# Front_panel.net
KiCad netlist of a schematic drawn in Altium Designer
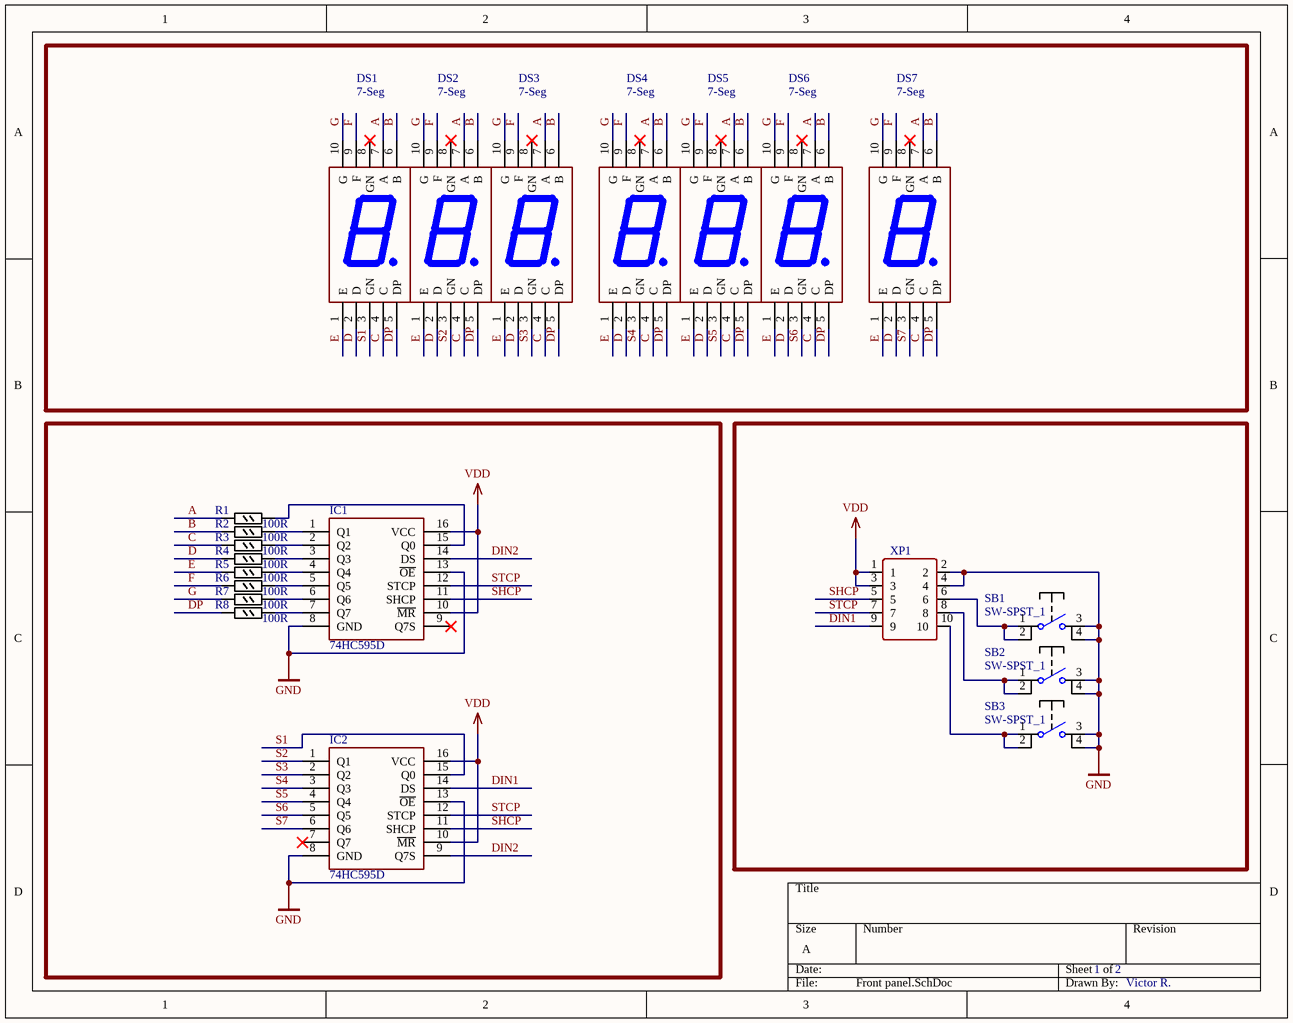
[diagram p0: Front panel.SchDoc]

(export (version "E")
  (design (tool "Eeschema 10.0.6"))
  (components
    (comp (ref "DS1")
      (value "7-Seg")
      (footprint "SamacSys:DIPS1524W51P254L1260H800Q10N")
      (description "Display")
      (fields (field (name "MANUFACTURER_PART_NUMBER") "4258"))
      (libsource (lib "SamacSys") (part "7-Seg"))
    )
    (comp (ref "DS2")
      (value "7-Seg")
      (footprint "SamacSys:DIPS1524W51P254L1260H800Q10N")
      (description "Display")
      (fields (field (name "MANUFACTURER_PART_NUMBER") "4258"))
      (libsource (lib "SamacSys") (part "7-Seg"))
    )
    (comp (ref "DS3")
      (value "7-Seg")
      (footprint "SamacSys:DIPS1524W51P254L1260H800Q10N")
      (description "Display")
      (fields (field (name "MANUFACTURER_PART_NUMBER") "4258"))
      (libsource (lib "SamacSys") (part "7-Seg"))
    )
    (comp (ref "DS4")
      (value "7-Seg")
      (footprint "SamacSys:DIPS1524W51P254L1260H800Q10N")
      (description "Display")
      (fields (field (name "MANUFACTURER_PART_NUMBER") "4258"))
      (libsource (lib "SamacSys") (part "7-Seg"))
    )
    (comp (ref "DS5")
      (value "7-Seg")
      (footprint "SamacSys:DIPS1524W51P254L1260H800Q10N")
      (description "Display")
      (fields (field (name "MANUFACTURER_PART_NUMBER") "4258"))
      (libsource (lib "SamacSys") (part "7-Seg"))
    )
    (comp (ref "DS6")
      (value "7-Seg")
      (footprint "SamacSys:DIPS1524W51P254L1260H800Q10N")
      (description "Display")
      (fields (field (name "MANUFACTURER_PART_NUMBER") "4258"))
      (libsource (lib "SamacSys") (part "7-Seg"))
    )
    (comp (ref "DS7")
      (value "7-Seg")
      (footprint "SamacSys:DIPS1524W51P254L1260H800Q10N")
      (description "Display")
      (fields (field (name "MANUFACTURER_PART_NUMBER") "4258"))
      (libsource (lib "SamacSys") (part "7-Seg"))
    )
    (comp (ref "IC1")
      (value "74HC595D")
      (footprint "SamacSys:SOIC127P600X175-16N")
      (description "Integrated Circuit")
      (libsource (lib "SamacSys") (part "74HC595D"))
    )
    (comp (ref "IC2")
      (value "74HC595D")
      (footprint "SamacSys:SOIC127P600X175-16N")
      (description "Integrated Circuit")
      (libsource (lib "SamacSys") (part "74HC595D"))
    )
    (comp (ref "R1")
      (value "100R")
      (footprint "RESC2012(0805)N")
      (fields (field (name "PART NUMBER") "RESC2012(0805)"))
      (libsource (lib "SssAccesDatbase") (part "Resistor 0,125W"))
    )
    (comp (ref "R2")
      (value "100R")
      (footprint "RESC2012(0805)N")
      (fields (field (name "PART NUMBER") "RESC2012(0805)"))
      (libsource (lib "SssAccesDatbase") (part "Resistor 0,125W"))
    )
    (comp (ref "R3")
      (value "100R")
      (footprint "RESC2012(0805)N")
      (fields (field (name "PART NUMBER") "RESC2012(0805)"))
      (libsource (lib "SssAccesDatbase") (part "Resistor 0,125W"))
    )
    (comp (ref "R4")
      (value "100R")
      (footprint "RESC2012(0805)N")
      (fields (field (name "PART NUMBER") "RESC2012(0805)"))
      (libsource (lib "SssAccesDatbase") (part "Resistor 0,125W"))
    )
    (comp (ref "R5")
      (value "100R")
      (footprint "RESC2012(0805)N")
      (fields (field (name "PART NUMBER") "RESC2012(0805)"))
      (libsource (lib "SssAccesDatbase") (part "Resistor 0,125W"))
    )
    (comp (ref "R6")
      (value "100R")
      (footprint "RESC2012(0805)N")
      (fields (field (name "PART NUMBER") "RESC2012(0805)"))
      (libsource (lib "SssAccesDatbase") (part "Resistor 0,125W"))
    )
    (comp (ref "R7")
      (value "100R")
      (footprint "RESC2012(0805)N")
      (fields (field (name "PART NUMBER") "RESC2012(0805)"))
      (libsource (lib "SssAccesDatbase") (part "Resistor 0,125W"))
    )
    (comp (ref "R8")
      (value "100R")
      (footprint "RESC2012(0805)N")
      (fields (field (name "PART NUMBER") "RESC2012(0805)"))
      (libsource (lib "SssAccesDatbase") (part "Resistor 0,125W"))
    )
    (comp (ref "SB1")
      (value "SW-SPST_1")
      (footprint "B3FS_SWITCH")
      (libsource (lib "SssAccesDatbase") (part "SW-SPST_1"))
    )
    (comp (ref "SB2")
      (value "SW-SPST_1")
      (footprint "B3FS_SWITCH")
      (libsource (lib "SssAccesDatbase") (part "SW-SPST_1"))
    )
    (comp (ref "SB3")
      (value "SW-SPST_1")
      (footprint "B3FS_SWITCH")
      (libsource (lib "SssAccesDatbase") (part "SW-SPST_1"))
    )
    (comp (ref "XP1")
      (value "BH-10")
      (footprint "BH-10")
      (description "Connector Header Through Hole 10 position 0.100\" (2.54mm)")
      (fields (field (name "PART NUMBER") "302-S101") (field (name "DIGI-KEY PART NUMBER") "ED1543-ND"))
      (libsource (lib "SssAccesDatbase") (part "XP-10"))
    )
  )
  (nets
    (net (code "1") (name "/A") (class "Default")
      (node (ref "DS1") (pin "7") (pinfunction "A_7") (pintype "passive"))
      (node (ref "DS2") (pin "7") (pinfunction "A_7") (pintype "passive"))
      (node (ref "DS3") (pin "7") (pinfunction "A_7") (pintype "passive"))
      (node (ref "DS4") (pin "7") (pinfunction "A_7") (pintype "passive"))
      (node (ref "DS5") (pin "7") (pinfunction "A_7") (pintype "passive"))
      (node (ref "DS6") (pin "7") (pinfunction "A_7") (pintype "passive"))
      (node (ref "DS7") (pin "7") (pinfunction "A_7") (pintype "passive"))
      (node (ref "R1") (pin "1") (pinfunction "1_1") (pintype "passive"))
    )
    (net (code "2") (name "/B") (class "Default")
      (node (ref "DS1") (pin "6") (pinfunction "B_6") (pintype "passive"))
      (node (ref "DS2") (pin "6") (pinfunction "B_6") (pintype "passive"))
      (node (ref "DS3") (pin "6") (pinfunction "B_6") (pintype "passive"))
      (node (ref "DS4") (pin "6") (pinfunction "B_6") (pintype "passive"))
      (node (ref "DS5") (pin "6") (pinfunction "B_6") (pintype "passive"))
      (node (ref "DS6") (pin "6") (pinfunction "B_6") (pintype "passive"))
      (node (ref "DS7") (pin "6") (pinfunction "B_6") (pintype "passive"))
      (node (ref "R2") (pin "1") (pinfunction "1_1") (pintype "passive"))
    )
    (net (code "3") (name "/C") (class "Default")
      (node (ref "DS1") (pin "4") (pinfunction "C_4") (pintype "passive"))
      (node (ref "DS2") (pin "4") (pinfunction "C_4") (pintype "passive"))
      (node (ref "DS3") (pin "4") (pinfunction "C_4") (pintype "passive"))
      (node (ref "DS4") (pin "4") (pinfunction "C_4") (pintype "passive"))
      (node (ref "DS5") (pin "4") (pinfunction "C_4") (pintype "passive"))
      (node (ref "DS6") (pin "4") (pinfunction "C_4") (pintype "passive"))
      (node (ref "DS7") (pin "4") (pinfunction "C_4") (pintype "passive"))
      (node (ref "R3") (pin "1") (pinfunction "1_1") (pintype "passive"))
    )
    (net (code "4") (name "/D") (class "Default")
      (node (ref "DS1") (pin "2") (pinfunction "D_2") (pintype "passive"))
      (node (ref "DS2") (pin "2") (pinfunction "D_2") (pintype "passive"))
      (node (ref "DS3") (pin "2") (pinfunction "D_2") (pintype "passive"))
      (node (ref "DS4") (pin "2") (pinfunction "D_2") (pintype "passive"))
      (node (ref "DS5") (pin "2") (pinfunction "D_2") (pintype "passive"))
      (node (ref "DS6") (pin "2") (pinfunction "D_2") (pintype "passive"))
      (node (ref "DS7") (pin "2") (pinfunction "D_2") (pintype "passive"))
      (node (ref "R4") (pin "1") (pinfunction "1_1") (pintype "passive"))
    )
    (net (code "5") (name "/DIN1") (class "Default")
      (node (ref "IC2") (pin "14") (pinfunction "DS_14") (pintype "passive"))
      (node (ref "XP1") (pin "9") (pinfunction "9_9") (pintype "passive"))
    )
    (net (code "6") (name "/DIN2") (class "Default")
      (node (ref "IC1") (pin "14") (pinfunction "DS_14") (pintype "passive"))
      (node (ref "IC2") (pin "9") (pinfunction "Q7S_9") (pintype "passive"))
    )
    (net (code "7") (name "/DP") (class "Default")
      (node (ref "DS1") (pin "5") (pinfunction "DP_5") (pintype "passive"))
      (node (ref "DS2") (pin "5") (pinfunction "DP_5") (pintype "passive"))
      (node (ref "DS3") (pin "5") (pinfunction "DP_5") (pintype "passive"))
      (node (ref "DS4") (pin "5") (pinfunction "DP_5") (pintype "passive"))
      (node (ref "DS5") (pin "5") (pinfunction "DP_5") (pintype "passive"))
      (node (ref "DS6") (pin "5") (pinfunction "DP_5") (pintype "passive"))
      (node (ref "DS7") (pin "5") (pinfunction "DP_5") (pintype "passive"))
      (node (ref "R8") (pin "1") (pinfunction "1_1") (pintype "passive"))
    )
    (net (code "8") (name "/E") (class "Default")
      (node (ref "DS1") (pin "1") (pinfunction "E_1") (pintype "passive"))
      (node (ref "DS2") (pin "1") (pinfunction "E_1") (pintype "passive"))
      (node (ref "DS3") (pin "1") (pinfunction "E_1") (pintype "passive"))
      (node (ref "DS4") (pin "1") (pinfunction "E_1") (pintype "passive"))
      (node (ref "DS5") (pin "1") (pinfunction "E_1") (pintype "passive"))
      (node (ref "DS6") (pin "1") (pinfunction "E_1") (pintype "passive"))
      (node (ref "DS7") (pin "1") (pinfunction "E_1") (pintype "passive"))
      (node (ref "R5") (pin "1") (pinfunction "1_1") (pintype "passive"))
    )
    (net (code "9") (name "/F") (class "Default")
      (node (ref "DS1") (pin "9") (pinfunction "F_9") (pintype "passive"))
      (node (ref "DS2") (pin "9") (pinfunction "F_9") (pintype "passive"))
      (node (ref "DS3") (pin "9") (pinfunction "F_9") (pintype "passive"))
      (node (ref "DS4") (pin "9") (pinfunction "F_9") (pintype "passive"))
      (node (ref "DS5") (pin "9") (pinfunction "F_9") (pintype "passive"))
      (node (ref "DS6") (pin "9") (pinfunction "F_9") (pintype "passive"))
      (node (ref "DS7") (pin "9") (pinfunction "F_9") (pintype "passive"))
      (node (ref "R6") (pin "1") (pinfunction "1_1") (pintype "passive"))
    )
    (net (code "10") (name "/G") (class "Default")
      (node (ref "DS1") (pin "10") (pinfunction "G_10") (pintype "passive"))
      (node (ref "DS2") (pin "10") (pinfunction "G_10") (pintype "passive"))
      (node (ref "DS3") (pin "10") (pinfunction "G_10") (pintype "passive"))
      (node (ref "DS4") (pin "10") (pinfunction "G_10") (pintype "passive"))
      (node (ref "DS5") (pin "10") (pinfunction "G_10") (pintype "passive"))
      (node (ref "DS6") (pin "10") (pinfunction "G_10") (pintype "passive"))
      (node (ref "DS7") (pin "10") (pinfunction "G_10") (pintype "passive"))
      (node (ref "R7") (pin "1") (pinfunction "1_1") (pintype "passive"))
    )
    (net (code "11") (name "/S1") (class "Default")
      (node (ref "DS1") (pin "3") (pinfunction "GN_3") (pintype "passive"))
      (node (ref "IC2") (pin "15") (pinfunction "Q0_15") (pintype "passive"))
    )
    (net (code "12") (name "/S2") (class "Default")
      (node (ref "DS2") (pin "3") (pinfunction "GN_3") (pintype "passive"))
      (node (ref "IC2") (pin "1") (pinfunction "Q1_1") (pintype "passive"))
    )
    (net (code "13") (name "/S3") (class "Default")
      (node (ref "DS3") (pin "3") (pinfunction "GN_3") (pintype "passive"))
      (node (ref "IC2") (pin "2") (pinfunction "Q2_2") (pintype "passive"))
    )
    (net (code "14") (name "/S4") (class "Default")
      (node (ref "DS4") (pin "3") (pinfunction "GN_3") (pintype "passive"))
      (node (ref "IC2") (pin "3") (pinfunction "Q3_3") (pintype "passive"))
    )
    (net (code "15") (name "/S5") (class "Default")
      (node (ref "DS5") (pin "3") (pinfunction "GN_3") (pintype "passive"))
      (node (ref "IC2") (pin "4") (pinfunction "Q4_4") (pintype "passive"))
    )
    (net (code "16") (name "/S6") (class "Default")
      (node (ref "DS6") (pin "3") (pinfunction "GN_3") (pintype "passive"))
      (node (ref "IC2") (pin "5") (pinfunction "Q5_5") (pintype "passive"))
    )
    (net (code "17") (name "/S7") (class "Default")
      (node (ref "DS7") (pin "3") (pinfunction "GN_3") (pintype "passive"))
      (node (ref "IC2") (pin "6") (pinfunction "Q6_6") (pintype "passive"))
    )
    (net (code "18") (name "/SHCP") (class "Default")
      (node (ref "IC1") (pin "11") (pinfunction "SHCP_11") (pintype "passive"))
      (node (ref "IC2") (pin "11") (pinfunction "SHCP_11") (pintype "passive"))
      (node (ref "XP1") (pin "5") (pinfunction "5_5") (pintype "passive"))
    )
    (net (code "19") (name "/STCP") (class "Default")
      (node (ref "IC1") (pin "12") (pinfunction "STCP_12") (pintype "passive"))
      (node (ref "IC2") (pin "12") (pinfunction "STCP_12") (pintype "passive"))
      (node (ref "XP1") (pin "7") (pinfunction "7_7") (pintype "passive"))
    )
    (net (code "20") (name "GND") (class "Default")
      (node (ref "IC1") (pin "13") (pinfunction "~{OE}_13") (pintype "passive"))
      (node (ref "IC1") (pin "8") (pinfunction "GND_8") (pintype "passive"))
      (node (ref "IC2") (pin "13") (pinfunction "~{OE}_13") (pintype "passive"))
      (node (ref "IC2") (pin "8") (pinfunction "GND_8") (pintype "passive"))
      (node (ref "SB1") (pin "3") (pinfunction "COMMON_3") (pintype "passive"))
      (node (ref "SB1") (pin "4") (pinfunction "COMMON_4") (pintype "passive"))
      (node (ref "SB2") (pin "3") (pinfunction "COMMON_3") (pintype "passive"))
      (node (ref "SB2") (pin "4") (pinfunction "COMMON_4") (pintype "passive"))
      (node (ref "SB3") (pin "3") (pinfunction "COMMON_3") (pintype "passive"))
      (node (ref "SB3") (pin "4") (pinfunction "COMMON_4") (pintype "passive"))
      (node (ref "XP1") (pin "2") (pinfunction "2_2") (pintype "passive"))
      (node (ref "XP1") (pin "4") (pinfunction "4_4") (pintype "passive"))
    )
    (net (code "21") (name "Net-(IC1-Q0)") (class "Default")
      (node (ref "IC1") (pin "15") (pinfunction "Q0_15") (pintype "passive"))
      (node (ref "R1") (pin "2") (pinfunction "2_2") (pintype "passive"))
    )
    (net (code "22") (name "Net-(IC1-Q1)") (class "Default")
      (node (ref "IC1") (pin "1") (pinfunction "Q1_1") (pintype "passive"))
      (node (ref "R2") (pin "2") (pinfunction "2_2") (pintype "passive"))
    )
    (net (code "23") (name "Net-(IC1-Q2)") (class "Default")
      (node (ref "IC1") (pin "2") (pinfunction "Q2_2") (pintype "passive"))
      (node (ref "R3") (pin "2") (pinfunction "2_2") (pintype "passive"))
    )
    (net (code "24") (name "Net-(IC1-Q3)") (class "Default")
      (node (ref "IC1") (pin "3") (pinfunction "Q3_3") (pintype "passive"))
      (node (ref "R4") (pin "2") (pinfunction "2_2") (pintype "passive"))
    )
    (net (code "25") (name "Net-(IC1-Q4)") (class "Default")
      (node (ref "IC1") (pin "4") (pinfunction "Q4_4") (pintype "passive"))
      (node (ref "R5") (pin "2") (pinfunction "2_2") (pintype "passive"))
    )
    (net (code "26") (name "Net-(IC1-Q5)") (class "Default")
      (node (ref "IC1") (pin "5") (pinfunction "Q5_5") (pintype "passive"))
      (node (ref "R6") (pin "2") (pinfunction "2_2") (pintype "passive"))
    )
    (net (code "27") (name "Net-(IC1-Q6)") (class "Default")
      (node (ref "IC1") (pin "6") (pinfunction "Q6_6") (pintype "passive"))
      (node (ref "R7") (pin "2") (pinfunction "2_2") (pintype "passive"))
    )
    (net (code "28") (name "Net-(IC1-Q7)") (class "Default")
      (node (ref "IC1") (pin "7") (pinfunction "Q7_7") (pintype "passive"))
      (node (ref "R8") (pin "2") (pinfunction "2_2") (pintype "passive"))
    )
    (net (code "29") (name "Net-(SB1-NO)") (class "Default")
      (node (ref "SB1") (pin "1") (pinfunction "COMMON_1") (pintype "passive"))
      (node (ref "SB1") (pin "2") (pinfunction "NO_2") (pintype "passive"))
      (node (ref "XP1") (pin "6") (pinfunction "6_6") (pintype "passive"))
    )
    (net (code "30") (name "Net-(SB2-NO)") (class "Default")
      (node (ref "SB2") (pin "1") (pinfunction "COMMON_1") (pintype "passive"))
      (node (ref "SB2") (pin "2") (pinfunction "NO_2") (pintype "passive"))
      (node (ref "XP1") (pin "8") (pinfunction "8_8") (pintype "passive"))
    )
    (net (code "31") (name "Net-(SB3-NO)") (class "Default")
      (node (ref "SB3") (pin "1") (pinfunction "COMMON_1") (pintype "passive"))
      (node (ref "SB3") (pin "2") (pinfunction "NO_2") (pintype "passive"))
      (node (ref "XP1") (pin "10") (pinfunction "10_10") (pintype "passive"))
    )
    (net (code "32") (name "VDD") (class "Default")
      (node (ref "IC1") (pin "10") (pinfunction "~{MR}_10") (pintype "passive"))
      (node (ref "IC1") (pin "16") (pinfunction "VCC_16") (pintype "passive"))
      (node (ref "IC2") (pin "10") (pinfunction "~{MR}_10") (pintype "passive"))
      (node (ref "IC2") (pin "16") (pinfunction "VCC_16") (pintype "passive"))
      (node (ref "XP1") (pin "1") (pinfunction "1_1") (pintype "passive"))
      (node (ref "XP1") (pin "3") (pinfunction "3_3") (pintype "passive"))
    )
    (net (code "33") (name "unconnected-(DS1-GN-Pad8)") (class "Default")
      (node (ref "DS1") (pin "8") (pinfunction "GN_8") (pintype "passive+no_connect"))
    )
    (net (code "34") (name "unconnected-(DS2-GN-Pad8)") (class "Default")
      (node (ref "DS2") (pin "8") (pinfunction "GN_8") (pintype "passive+no_connect"))
    )
    (net (code "35") (name "unconnected-(DS3-GN-Pad8)") (class "Default")
      (node (ref "DS3") (pin "8") (pinfunction "GN_8") (pintype "passive+no_connect"))
    )
    (net (code "36") (name "unconnected-(DS4-GN-Pad8)") (class "Default")
      (node (ref "DS4") (pin "8") (pinfunction "GN_8") (pintype "passive+no_connect"))
    )
    (net (code "37") (name "unconnected-(DS5-GN-Pad8)") (class "Default")
      (node (ref "DS5") (pin "8") (pinfunction "GN_8") (pintype "passive+no_connect"))
    )
    (net (code "38") (name "unconnected-(DS6-GN-Pad8)") (class "Default")
      (node (ref "DS6") (pin "8") (pinfunction "GN_8") (pintype "passive+no_connect"))
    )
    (net (code "39") (name "unconnected-(DS7-GN-Pad8)") (class "Default")
      (node (ref "DS7") (pin "8") (pinfunction "GN_8") (pintype "passive+no_connect"))
    )
    (net (code "40") (name "unconnected-(IC1-Q7S-Pad9)") (class "Default")
      (node (ref "IC1") (pin "9") (pinfunction "Q7S_9") (pintype "passive+no_connect"))
    )
    (net (code "41") (name "unconnected-(IC2-Q7-Pad7)") (class "Default")
      (node (ref "IC2") (pin "7") (pinfunction "Q7_7") (pintype "passive+no_connect"))
    )
  )
)
